# audibleCore.net
KiCad netlist of a schematic drawn in EAGLE
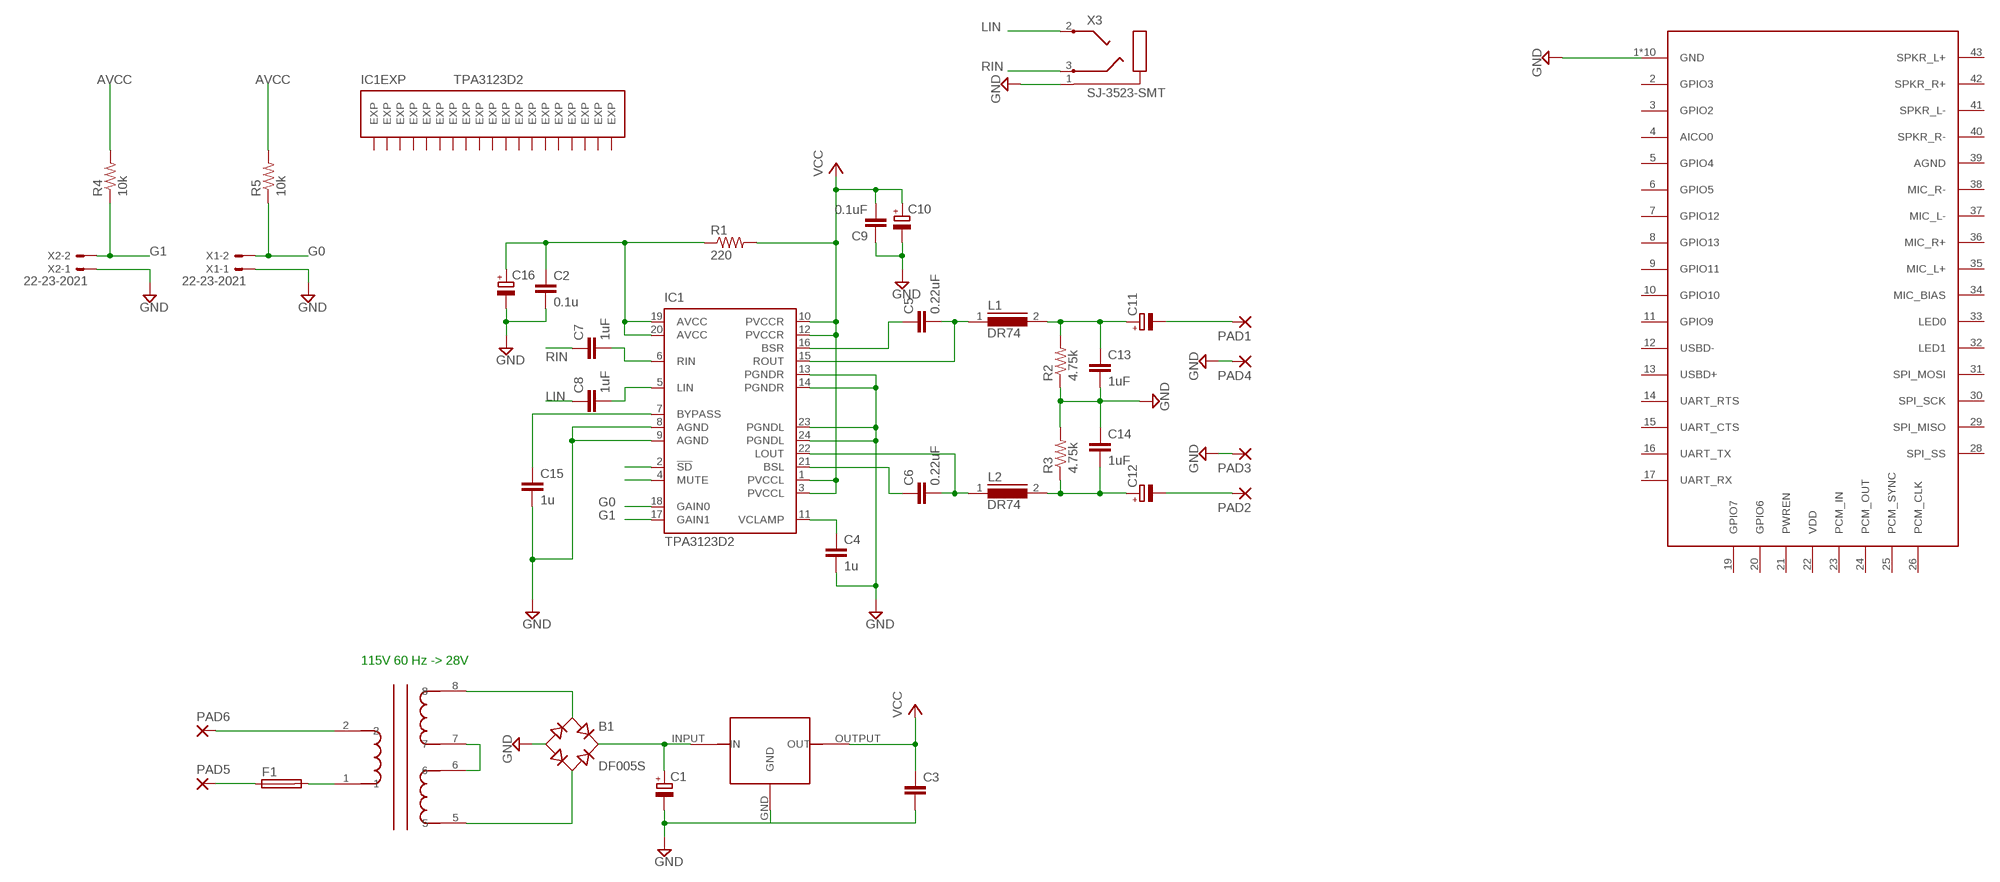
[diagram p0: schematic, sheet 1]

(export (version "E")
  (design (tool "Eeschema 10.0.6"))
  (components
    (comp (ref "B1")
      (value "DF005S")
      (footprint "eagle-import:DFS")
      (libsource (lib "eagle-import") (part "DFS005"))
    )
    (comp (ref "C1")
      (value "CPOL-EUG")
      (footprint "eagle-import:PANASONIC_G")
      (libsource (lib "eagle-import") (part "CPOL-EUG"))
    )
    (comp (ref "C2")
      (value "0.1u")
      (footprint "eagle-import:C1206")
      (libsource (lib "eagle-import") (part "C-EUC1206"))
    )
    (comp (ref "C3")
      (value "C-EUC1206")
      (footprint "eagle-import:C1206")
      (libsource (lib "eagle-import") (part "C-EUC1206"))
    )
    (comp (ref "C4")
      (value "1u")
      (footprint "eagle-import:C1206")
      (libsource (lib "eagle-import") (part "C-EUC1206"))
    )
    (comp (ref "C5")
      (value "0.22uF")
      (footprint "eagle-import:C1206")
      (libsource (lib "eagle-import") (part "C-EUC1206"))
    )
    (comp (ref "C6")
      (value "0.22uF")
      (footprint "eagle-import:C1206")
      (libsource (lib "eagle-import") (part "C-EUC1206"))
    )
    (comp (ref "C7")
      (value "1uF")
      (footprint "eagle-import:C1206")
      (libsource (lib "eagle-import") (part "C-EUC1206"))
    )
    (comp (ref "C8")
      (value "1uF")
      (footprint "eagle-import:C1206")
      (libsource (lib "eagle-import") (part "C-EUC1206"))
    )
    (comp (ref "C9")
      (value "0.1uF")
      (footprint "eagle-import:C1206")
      (libsource (lib "eagle-import") (part "C-EUC1206"))
    )
    (comp (ref "C10")
      (value "CPOL-EUG")
      (footprint "eagle-import:PANASONIC_G")
      (libsource (lib "eagle-import") (part "CPOL-EUG"))
    )
    (comp (ref "C11")
      (value "CPOL-EUG")
      (footprint "eagle-import:PANASONIC_G")
      (libsource (lib "eagle-import") (part "CPOL-EUG"))
    )
    (comp (ref "C12")
      (value "CPOL-EUG")
      (footprint "eagle-import:PANASONIC_G")
      (libsource (lib "eagle-import") (part "CPOL-EUG"))
    )
    (comp (ref "C13")
      (value "1uF")
      (footprint "eagle-import:C1206")
      (libsource (lib "eagle-import") (part "C-EUC1206"))
    )
    (comp (ref "C14")
      (value "1uF")
      (footprint "eagle-import:C1206")
      (libsource (lib "eagle-import") (part "C-EUC1206"))
    )
    (comp (ref "C15")
      (value "1u")
      (footprint "eagle-import:C1206")
      (libsource (lib "eagle-import") (part "C-EUC1206"))
    )
    (comp (ref "C16")
      (value "CPOL-EUG")
      (footprint "eagle-import:PANASONIC_G")
      (libsource (lib "eagle-import") (part "CPOL-EUG"))
    )
    (comp (ref "F1")
      (value "GSH15")
      (footprint "eagle-import:GSH15")
      (fields (field (name "MPN") "64900001039"))
      (libsource (lib "eagle-import") (part "GSH15"))
    )
    (comp (ref "IC1")
      (value "TPA3123D2")
      (footprint "eagle-import:PWP-TSSOP24")
      (fields (field (name "MPN") "TPA3123D2PWP"))
      (libsource (lib "eagle-import") (part "TPA3123D2"))
    )
    (comp (ref "L1")
      (value "DR74")
      (footprint "eagle-import:DR74")
      (libsource (lib "eagle-import") (part "DR74"))
    )
    (comp (ref "L2")
      (value "DR74")
      (footprint "eagle-import:DR74")
      (libsource (lib "eagle-import") (part "DR74"))
    )
    (comp (ref "PAD1")
      (value "SMD5")
      (footprint "eagle-import:SMD2,54-5,08")
      (libsource (lib "eagle-import") (part "SMD5"))
    )
    (comp (ref "PAD2")
      (value "SMD5")
      (footprint "eagle-import:SMD2,54-5,08")
      (libsource (lib "eagle-import") (part "SMD5"))
    )
    (comp (ref "PAD3")
      (value "SMD5")
      (footprint "eagle-import:SMD2,54-5,08")
      (libsource (lib "eagle-import") (part "SMD5"))
    )
    (comp (ref "PAD4")
      (value "SMD5")
      (footprint "eagle-import:SMD2,54-5,08")
      (libsource (lib "eagle-import") (part "SMD5"))
    )
    (comp (ref "PAD5")
      (value "SMD5")
      (footprint "eagle-import:SMD2,54-5,08")
      (libsource (lib "eagle-import") (part "SMD5"))
    )
    (comp (ref "PAD6")
      (value "SMD5")
      (footprint "eagle-import:SMD2,54-5,08")
      (libsource (lib "eagle-import") (part "SMD5"))
    )
    (comp (ref "R1")
      (value "220")
      (footprint "eagle-import:R1206")
      (libsource (lib "eagle-import") (part "R-US_R1206"))
    )
    (comp (ref "R2")
      (value "4.75k")
      (footprint "eagle-import:R1206")
      (libsource (lib "eagle-import") (part "R-US_R1206"))
    )
    (comp (ref "R3")
      (value "4.75k")
      (footprint "eagle-import:R1206")
      (libsource (lib "eagle-import") (part "R-US_R1206"))
    )
    (comp (ref "R4")
      (value "10k")
      (footprint "eagle-import:R1206")
      (libsource (lib "eagle-import") (part "R-US_R1206"))
    )
    (comp (ref "R5")
      (value "10k")
      (footprint "eagle-import:R1206")
      (libsource (lib "eagle-import") (part "R-US_R1206"))
    )
    (comp (ref "U$1")
      (value "ST-7-24")
      (footprint "eagle-import:ST-7")
      (libsource (lib "eagle-import") (part "ST-7-24"))
    )
    (comp (ref "U$2")
      (value "L78XX")
      (footprint "eagle-import:D2PAK")
      (libsource (lib "eagle-import") (part "L78XX"))
    )
    (comp (ref "U$3")
      (value "RN-52")
      (footprint "eagle-import:RN-52")
      (libsource (lib "eagle-import") (part "RN-52"))
    )
    (comp (ref "X1")
      (value "22-23-2021")
      (footprint "eagle-import:22-23-2021")
      (fields (field (name "MF") "MOLEX"))
      (libsource (lib "eagle-import") (part "22-23-2021"))
    )
    (comp (ref "X2")
      (value "22-23-2021")
      (footprint "eagle-import:22-23-2021")
      (fields (field (name "MF") "MOLEX"))
      (libsource (lib "eagle-import") (part "22-23-2021"))
    )
    (comp (ref "X3")
      (value "SJ-3523-SMT")
      (footprint "eagle-import:SJ-3523-SMT")
      (libsource (lib "eagle-import") (part "SJ-3523-SMT"))
    )
  )
  (nets
    (net (code "1") (name "/AVCC") (class "Default")
      (node (ref "C16") (pin "+") (pinfunction "+_+") (pintype "passive"))
      (node (ref "C2") (pin "1") (pinfunction "1_1") (pintype "passive"))
      (node (ref "IC1") (pin "19") (pinfunction "AVCC_19") (pintype "input"))
      (node (ref "IC1") (pin "20") (pinfunction "AVCC_20") (pintype "input"))
      (node (ref "R1") (pin "1") (pinfunction "1_1") (pintype "passive"))
      (node (ref "R4") (pin "2") (pinfunction "2_2") (pintype "passive"))
      (node (ref "R5") (pin "2") (pinfunction "2_2") (pintype "passive"))
    )
    (net (code "2") (name "/G0") (class "Default")
      (node (ref "IC1") (pin "18") (pinfunction "GAIN0_18") (pintype "input"))
      (node (ref "R5") (pin "1") (pinfunction "1_1") (pintype "passive"))
      (node (ref "X1") (pin "2") (pinfunction "S_2") (pintype "passive"))
    )
    (net (code "3") (name "/G1") (class "Default")
      (node (ref "IC1") (pin "17") (pinfunction "GAIN1_17") (pintype "input"))
      (node (ref "R4") (pin "1") (pinfunction "1_1") (pintype "passive"))
      (node (ref "X2") (pin "2") (pinfunction "S_2") (pintype "passive"))
    )
    (net (code "4") (name "/LIN") (class "Default")
      (node (ref "C8") (pin "1") (pinfunction "1_1") (pintype "passive"))
      (node (ref "X3") (pin "2") (pinfunction "TIP_2") (pintype "passive"))
    )
    (net (code "5") (name "/RIN") (class "Default")
      (node (ref "C7") (pin "1") (pinfunction "1_1") (pintype "passive"))
      (node (ref "X3") (pin "3") (pinfunction "RING_3") (pintype "passive"))
    )
    (net (code "6") (name "GND") (class "Default")
      (node (ref "B1") (pin "-") (pinfunction "-_-") (pintype "passive"))
      (node (ref "C1") (pin "-") (pinfunction "-_-") (pintype "passive"))
      (node (ref "C10") (pin "-") (pinfunction "-_-") (pintype "passive"))
      (node (ref "C13") (pin "2") (pinfunction "2_2") (pintype "passive"))
      (node (ref "C14") (pin "1") (pinfunction "1_1") (pintype "passive"))
      (node (ref "C15") (pin "2") (pinfunction "2_2") (pintype "passive"))
      (node (ref "C16") (pin "-") (pinfunction "-_-") (pintype "passive"))
      (node (ref "C2") (pin "2") (pinfunction "2_2") (pintype "passive"))
      (node (ref "C3") (pin "2") (pinfunction "2_2") (pintype "passive"))
      (node (ref "C4") (pin "2") (pinfunction "2_2") (pintype "passive"))
      (node (ref "C9") (pin "1") (pinfunction "1_1") (pintype "passive"))
      (node (ref "IC1") (pin "13") (pinfunction "PGNDR_13") (pintype "input"))
      (node (ref "IC1") (pin "14") (pinfunction "PGNDR_14") (pintype "input"))
      (node (ref "IC1") (pin "23") (pinfunction "PGNDL_23") (pintype "input"))
      (node (ref "IC1") (pin "24") (pinfunction "PGNDL_24") (pintype "input"))
      (node (ref "IC1") (pin "8") (pinfunction "AGND_8") (pintype "input"))
      (node (ref "IC1") (pin "9") (pinfunction "AGND_9") (pintype "input"))
      (node (ref "PAD3") (pin "1") (pinfunction "P_1") (pintype "passive"))
      (node (ref "PAD4") (pin "1") (pinfunction "P_1") (pintype "passive"))
      (node (ref "R2") (pin "1") (pinfunction "1_1") (pintype "passive"))
      (node (ref "R3") (pin "2") (pinfunction "2_2") (pintype "passive"))
      (node (ref "U$2") (pin "GND") (pinfunction "GND_GND") (pintype "bidirectional"))
      (node (ref "U$3") (pin "1") (pinfunction "GND_1") (pintype "bidirectional"))
      (node (ref "U$3") (pin "18") (pinfunction "GND_18") (pintype "bidirectional"))
      (node (ref "U$3") (pin "27") (pinfunction "GND_27") (pintype "bidirectional"))
      (node (ref "U$3") (pin "44") (pinfunction "GND_44") (pintype "bidirectional"))
      (node (ref "U$3") (pin "45") (pinfunction "GND_45") (pintype "bidirectional"))
      (node (ref "U$3") (pin "46") (pinfunction "GND_46") (pintype "bidirectional"))
      (node (ref "U$3") (pin "47") (pinfunction "GND_47") (pintype "bidirectional"))
      (node (ref "U$3") (pin "48") (pinfunction "GND_48") (pintype "bidirectional"))
      (node (ref "U$3") (pin "49") (pinfunction "GND_49") (pintype "bidirectional"))
      (node (ref "U$3") (pin "50") (pinfunction "GND_50") (pintype "bidirectional"))
      (node (ref "X1") (pin "1") (pinfunction "S_1") (pintype "passive"))
      (node (ref "X2") (pin "1") (pinfunction "S_1") (pintype "passive"))
      (node (ref "X3") (pin "1") (pinfunction "EARTH_1") (pintype "passive"))
    )
    (net (code "7") (name "Net-(B1-PadAC1)") (class "Default")
      (node (ref "B1") (pin "AC1") (pinfunction "AC1_AC1") (pintype "passive"))
      (node (ref "U$1") (pin "8") (pinfunction "8_8") (pintype "bidirectional"))
    )
    (net (code "8") (name "Net-(B1-PadAC2)") (class "Default")
      (node (ref "B1") (pin "AC2") (pinfunction "AC2_AC2") (pintype "passive"))
      (node (ref "U$1") (pin "5") (pinfunction "5_5") (pintype "bidirectional"))
    )
    (net (code "9") (name "Net-(C11-Pad+)") (class "Default")
      (node (ref "C11") (pin "+") (pinfunction "+_+") (pintype "passive"))
      (node (ref "C13") (pin "1") (pinfunction "1_1") (pintype "passive"))
      (node (ref "L1") (pin "2") (pinfunction "2_2") (pintype "passive"))
      (node (ref "R2") (pin "2") (pinfunction "2_2") (pintype "passive"))
    )
    (net (code "10") (name "Net-(C12-Pad+)") (class "Default")
      (node (ref "C12") (pin "+") (pinfunction "+_+") (pintype "passive"))
      (node (ref "C14") (pin "2") (pinfunction "2_2") (pintype "passive"))
      (node (ref "L2") (pin "2") (pinfunction "2_2") (pintype "passive"))
      (node (ref "R3") (pin "1") (pinfunction "1_1") (pintype "passive"))
    )
    (net (code "11") (name "Net-(F1-Pad2)") (class "Default")
      (node (ref "F1") (pin "2") (pinfunction "2_2") (pintype "passive"))
      (node (ref "U$1") (pin "1") (pinfunction "1_1") (pintype "bidirectional"))
    )
    (net (code "12") (name "Net-(IC1B-BSL)") (class "Default")
      (node (ref "C6") (pin "1") (pinfunction "1_1") (pintype "passive"))
      (node (ref "IC1") (pin "21") (pinfunction "BSL_21") (pintype "passive"))
    )
    (net (code "13") (name "Net-(IC1B-BSR)") (class "Default")
      (node (ref "C5") (pin "1") (pinfunction "1_1") (pintype "passive"))
      (node (ref "IC1") (pin "16") (pinfunction "BSR_16") (pintype "passive"))
    )
    (net (code "14") (name "Net-(IC1B-BYPASS)") (class "Default")
      (node (ref "C15") (pin "1") (pinfunction "1_1") (pintype "passive"))
      (node (ref "IC1") (pin "7") (pinfunction "BYPASS_7") (pintype "input"))
    )
    (net (code "15") (name "Net-(IC1B-LIN)") (class "Default")
      (node (ref "C8") (pin "2") (pinfunction "2_2") (pintype "passive"))
      (node (ref "IC1") (pin "5") (pinfunction "LIN_5") (pintype "input"))
    )
    (net (code "16") (name "Net-(IC1B-LOUT)") (class "Default")
      (node (ref "C6") (pin "2") (pinfunction "2_2") (pintype "passive"))
      (node (ref "IC1") (pin "22") (pinfunction "LOUT_22") (pintype "output"))
      (node (ref "L2") (pin "1") (pinfunction "1_1") (pintype "passive"))
    )
    (net (code "17") (name "Net-(IC1B-RIN)") (class "Default")
      (node (ref "C7") (pin "2") (pinfunction "2_2") (pintype "passive"))
      (node (ref "IC1") (pin "6") (pinfunction "RIN_6") (pintype "input"))
    )
    (net (code "18") (name "Net-(IC1B-ROUT)") (class "Default")
      (node (ref "C5") (pin "2") (pinfunction "2_2") (pintype "passive"))
      (node (ref "IC1") (pin "15") (pinfunction "ROUT_15") (pintype "output"))
      (node (ref "L1") (pin "1") (pinfunction "1_1") (pintype "passive"))
    )
    (net (code "19") (name "Net-(IC1B-VCLAMP)") (class "Default")
      (node (ref "C4") (pin "1") (pinfunction "1_1") (pintype "passive"))
      (node (ref "IC1") (pin "11") (pinfunction "VCLAMP_11") (pintype "input"))
    )
    (net (code "20") (name "Net-(PAD1-P)") (class "Default")
      (node (ref "C11") (pin "-") (pinfunction "-_-") (pintype "passive"))
      (node (ref "PAD1") (pin "1") (pinfunction "P_1") (pintype "passive"))
    )
    (net (code "21") (name "Net-(PAD2-P)") (class "Default")
      (node (ref "C12") (pin "-") (pinfunction "-_-") (pintype "passive"))
      (node (ref "PAD2") (pin "1") (pinfunction "P_1") (pintype "passive"))
    )
    (net (code "22") (name "Net-(PAD5-P)") (class "Default")
      (node (ref "F1") (pin "1") (pinfunction "1_1") (pintype "passive"))
      (node (ref "PAD5") (pin "1") (pinfunction "P_1") (pintype "passive"))
    )
    (net (code "23") (name "Net-(PAD6-P)") (class "Default")
      (node (ref "PAD6") (pin "1") (pinfunction "P_1") (pintype "passive"))
      (node (ref "U$1") (pin "2") (pinfunction "2_2") (pintype "bidirectional"))
    )
    (net (code "24") (name "Net-(U$1-Pad6)") (class "Default")
      (node (ref "U$1") (pin "6") (pinfunction "6_6") (pintype "bidirectional"))
      (node (ref "U$1") (pin "7") (pinfunction "7_7") (pintype "bidirectional"))
    )
    (net (code "25") (name "Net-(U$2-IN)") (class "Default")
      (node (ref "B1") (pin "+") (pinfunction "+_+") (pintype "passive"))
      (node (ref "C1") (pin "+") (pinfunction "+_+") (pintype "passive"))
      (node (ref "U$2") (pin "INPUT") (pinfunction "IN_INPUT") (pintype "bidirectional"))
    )
    (net (code "26") (name "VCC") (class "Default")
      (node (ref "C10") (pin "+") (pinfunction "+_+") (pintype "passive"))
      (node (ref "C3") (pin "1") (pinfunction "1_1") (pintype "passive"))
      (node (ref "C9") (pin "2") (pinfunction "2_2") (pintype "passive"))
      (node (ref "IC1") (pin "1") (pinfunction "PVCCL_1") (pintype "input"))
      (node (ref "IC1") (pin "10") (pinfunction "PVCCR_10") (pintype "input"))
      (node (ref "IC1") (pin "12") (pinfunction "PVCCR_12") (pintype "input"))
      (node (ref "IC1") (pin "3") (pinfunction "PVCCL_3") (pintype "input"))
      (node (ref "R1") (pin "2") (pinfunction "2_2") (pintype "passive"))
      (node (ref "U$2") (pin "OUTPUT") (pinfunction "OUT_OUTPUT") (pintype "bidirectional"))
    )
    (net (code "27") (name "unconnected-(IC1-PadEXP)") (class "Default")
      (node (ref "IC1") (pin "EXP") (pinfunction "EXP_EXP") (pintype "passive"))
    )
    (net (code "28") (name "unconnected-(IC1A-EXP-PadEXP@1)") (class "Default")
      (node (ref "IC1") (pin "EXP@1") (pinfunction "EXP_EXP@1") (pintype "passive"))
    )
    (net (code "29") (name "unconnected-(IC1A-EXP-PadEXP@2)") (class "Default")
      (node (ref "IC1") (pin "EXP@2") (pinfunction "EXP_EXP@2") (pintype "passive"))
    )
    (net (code "30") (name "unconnected-(IC1A-EXP-PadEXP@3)") (class "Default")
      (node (ref "IC1") (pin "EXP@3") (pinfunction "EXP_EXP@3") (pintype "passive"))
    )
    (net (code "31") (name "unconnected-(IC1A-EXP-PadEXP@4)") (class "Default")
      (node (ref "IC1") (pin "EXP@4") (pinfunction "EXP_EXP@4") (pintype "passive"))
    )
    (net (code "32") (name "unconnected-(IC1A-EXP-PadEXP@5)") (class "Default")
      (node (ref "IC1") (pin "EXP@5") (pinfunction "EXP_EXP@5") (pintype "passive"))
    )
    (net (code "33") (name "unconnected-(IC1A-EXP-PadEXP@6)") (class "Default")
      (node (ref "IC1") (pin "EXP@6") (pinfunction "EXP_EXP@6") (pintype "passive"))
    )
    (net (code "34") (name "unconnected-(IC1A-EXP-PadEXP@7)") (class "Default")
      (node (ref "IC1") (pin "EXP@7") (pinfunction "EXP_EXP@7") (pintype "passive"))
    )
    (net (code "35") (name "unconnected-(IC1A-EXP-PadEXP@8)") (class "Default")
      (node (ref "IC1") (pin "EXP@8") (pinfunction "EXP_EXP@8") (pintype "passive"))
    )
    (net (code "36") (name "unconnected-(IC1A-EXP-PadEXP@9)") (class "Default")
      (node (ref "IC1") (pin "EXP@9") (pinfunction "EXP_EXP@9") (pintype "passive"))
    )
    (net (code "37") (name "unconnected-(IC1A-EXP-PadEXP@10)") (class "Default")
      (node (ref "IC1") (pin "EXP@10") (pinfunction "EXP_EXP@10") (pintype "passive"))
    )
    (net (code "38") (name "unconnected-(IC1A-EXP-PadEXP@11)") (class "Default")
      (node (ref "IC1") (pin "EXP@11") (pinfunction "EXP_EXP@11") (pintype "passive"))
    )
    (net (code "39") (name "unconnected-(IC1A-EXP-PadEXP@12)") (class "Default")
      (node (ref "IC1") (pin "EXP@12") (pinfunction "EXP_EXP@12") (pintype "passive"))
    )
    (net (code "40") (name "unconnected-(IC1A-EXP-PadEXP@13)") (class "Default")
      (node (ref "IC1") (pin "EXP@13") (pinfunction "EXP_EXP@13") (pintype "passive"))
    )
    (net (code "41") (name "unconnected-(IC1A-EXP-PadEXP@14)") (class "Default")
      (node (ref "IC1") (pin "EXP@14") (pinfunction "EXP_EXP@14") (pintype "passive"))
    )
    (net (code "42") (name "unconnected-(IC1A-EXP-PadEXP@15)") (class "Default")
      (node (ref "IC1") (pin "EXP@15") (pinfunction "EXP_EXP@15") (pintype "passive"))
    )
    (net (code "43") (name "unconnected-(IC1A-EXP-PadEXP@16)") (class "Default")
      (node (ref "IC1") (pin "EXP@16") (pinfunction "EXP_EXP@16") (pintype "passive"))
    )
    (net (code "44") (name "unconnected-(IC1A-EXP-PadEXP@17)") (class "Default")
      (node (ref "IC1") (pin "EXP@17") (pinfunction "EXP_EXP@17") (pintype "passive"))
    )
    (net (code "45") (name "unconnected-(IC1A-EXP-PadEXP@18)") (class "Default")
      (node (ref "IC1") (pin "EXP@18") (pinfunction "EXP_EXP@18") (pintype "passive"))
    )
    (net (code "46") (name "unconnected-(IC1B-MUTE-Pad4)") (class "Default")
      (node (ref "IC1") (pin "4") (pinfunction "MUTE_4") (pintype "input"))
    )
    (net (code "47") (name "unconnected-(IC1B-~{SD}-Pad2)") (class "Default")
      (node (ref "IC1") (pin "2") (pinfunction "~{SD}_2") (pintype "input"))
    )
    (net (code "48") (name "unconnected-(U$3-AGND-Pad39)") (class "Default")
      (node (ref "U$3") (pin "39") (pinfunction "AGND_39") (pintype "bidirectional"))
    )
    (net (code "49") (name "unconnected-(U$3-AICO0-Pad4)") (class "Default")
      (node (ref "U$3") (pin "4") (pinfunction "AICO0_4") (pintype "bidirectional"))
    )
    (net (code "50") (name "unconnected-(U$3-GPIO2-Pad3)") (class "Default")
      (node (ref "U$3") (pin "3") (pinfunction "GPIO2_3") (pintype "bidirectional"))
    )
    (net (code "51") (name "unconnected-(U$3-GPIO3-Pad2)") (class "Default")
      (node (ref "U$3") (pin "2") (pinfunction "GPIO3_2") (pintype "bidirectional"))
    )
    (net (code "52") (name "unconnected-(U$3-GPIO4-Pad5)") (class "Default")
      (node (ref "U$3") (pin "5") (pinfunction "GPIO4_5") (pintype "bidirectional"))
    )
    (net (code "53") (name "unconnected-(U$3-GPIO5-Pad6)") (class "Default")
      (node (ref "U$3") (pin "6") (pinfunction "GPIO5_6") (pintype "bidirectional"))
    )
    (net (code "54") (name "unconnected-(U$3-GPIO6-Pad20)") (class "Default")
      (node (ref "U$3") (pin "20") (pinfunction "GPIO6_20") (pintype "bidirectional"))
    )
    (net (code "55") (name "unconnected-(U$3-GPIO7-Pad19)") (class "Default")
      (node (ref "U$3") (pin "19") (pinfunction "GPIO7_19") (pintype "bidirectional"))
    )
    (net (code "56") (name "unconnected-(U$3-GPIO9-Pad11)") (class "Default")
      (node (ref "U$3") (pin "11") (pinfunction "GPIO9_11") (pintype "bidirectional"))
    )
    (net (code "57") (name "unconnected-(U$3-GPIO10-Pad10)") (class "Default")
      (node (ref "U$3") (pin "10") (pinfunction "GPIO10_10") (pintype "bidirectional"))
    )
    (net (code "58") (name "unconnected-(U$3-GPIO11-Pad9)") (class "Default")
      (node (ref "U$3") (pin "9") (pinfunction "GPIO11_9") (pintype "bidirectional"))
    )
    (net (code "59") (name "unconnected-(U$3-GPIO12-Pad7)") (class "Default")
      (node (ref "U$3") (pin "7") (pinfunction "GPIO12_7") (pintype "bidirectional"))
    )
    (net (code "60") (name "unconnected-(U$3-GPIO13-Pad8)") (class "Default")
      (node (ref "U$3") (pin "8") (pinfunction "GPIO13_8") (pintype "bidirectional"))
    )
    (net (code "61") (name "unconnected-(U$3-LED0-Pad33)") (class "Default")
      (node (ref "U$3") (pin "33") (pinfunction "LED0_33") (pintype "bidirectional"))
    )
    (net (code "62") (name "unconnected-(U$3-LED1-Pad32)") (class "Default")
      (node (ref "U$3") (pin "32") (pinfunction "LED1_32") (pintype "bidirectional"))
    )
    (net (code "63") (name "unconnected-(U$3-MIC_BIAS-Pad34)") (class "Default")
      (node (ref "U$3") (pin "34") (pinfunction "MIC_BIAS_34") (pintype "bidirectional"))
    )
    (net (code "64") (name "unconnected-(U$3-MIC_L+-Pad35)") (class "Default")
      (node (ref "U$3") (pin "35") (pinfunction "MIC_L+_35") (pintype "bidirectional"))
    )
    (net (code "65") (name "unconnected-(U$3-MIC_L--Pad37)") (class "Default")
      (node (ref "U$3") (pin "37") (pinfunction "MIC_L-_37") (pintype "bidirectional"))
    )
    (net (code "66") (name "unconnected-(U$3-MIC_R+-Pad36)") (class "Default")
      (node (ref "U$3") (pin "36") (pinfunction "MIC_R+_36") (pintype "bidirectional"))
    )
    (net (code "67") (name "unconnected-(U$3-MIC_R--Pad38)") (class "Default")
      (node (ref "U$3") (pin "38") (pinfunction "MIC_R-_38") (pintype "bidirectional"))
    )
    (net (code "68") (name "unconnected-(U$3-PCM_CLK-Pad26)") (class "Default")
      (node (ref "U$3") (pin "26") (pinfunction "PCM_CLK_26") (pintype "bidirectional"))
    )
    (net (code "69") (name "unconnected-(U$3-PCM_IN-Pad23)") (class "Default")
      (node (ref "U$3") (pin "23") (pinfunction "PCM_IN_23") (pintype "bidirectional"))
    )
    (net (code "70") (name "unconnected-(U$3-PCM_OUT-Pad24)") (class "Default")
      (node (ref "U$3") (pin "24") (pinfunction "PCM_OUT_24") (pintype "bidirectional"))
    )
    (net (code "71") (name "unconnected-(U$3-PCM_SYNC-Pad25)") (class "Default")
      (node (ref "U$3") (pin "25") (pinfunction "PCM_SYNC_25") (pintype "bidirectional"))
    )
    (net (code "72") (name "unconnected-(U$3-PWREN-Pad21)") (class "Default")
      (node (ref "U$3") (pin "21") (pinfunction "PWREN_21") (pintype "bidirectional"))
    )
    (net (code "73") (name "unconnected-(U$3-SPI_MISO-Pad29)") (class "Default")
      (node (ref "U$3") (pin "29") (pinfunction "SPI_MISO_29") (pintype "bidirectional"))
    )
    (net (code "74") (name "unconnected-(U$3-SPI_MOSI-Pad31)") (class "Default")
      (node (ref "U$3") (pin "31") (pinfunction "SPI_MOSI_31") (pintype "bidirectional"))
    )
    (net (code "75") (name "unconnected-(U$3-SPI_SCK-Pad30)") (class "Default")
      (node (ref "U$3") (pin "30") (pinfunction "SPI_SCK_30") (pintype "bidirectional"))
    )
    (net (code "76") (name "unconnected-(U$3-SPI_SS-Pad28)") (class "Default")
      (node (ref "U$3") (pin "28") (pinfunction "SPI_SS_28") (pintype "bidirectional"))
    )
    (net (code "77") (name "unconnected-(U$3-SPKR_L+-Pad43)") (class "Default")
      (node (ref "U$3") (pin "43") (pinfunction "SPKR_L+_43") (pintype "bidirectional"))
    )
    (net (code "78") (name "unconnected-(U$3-SPKR_L--Pad41)") (class "Default")
      (node (ref "U$3") (pin "41") (pinfunction "SPKR_L-_41") (pintype "bidirectional"))
    )
    (net (code "79") (name "unconnected-(U$3-SPKR_R+-Pad42)") (class "Default")
      (node (ref "U$3") (pin "42") (pinfunction "SPKR_R+_42") (pintype "bidirectional"))
    )
    (net (code "80") (name "unconnected-(U$3-SPKR_R--Pad40)") (class "Default")
      (node (ref "U$3") (pin "40") (pinfunction "SPKR_R-_40") (pintype "bidirectional"))
    )
    (net (code "81") (name "unconnected-(U$3-UART_CTS-Pad15)") (class "Default")
      (node (ref "U$3") (pin "15") (pinfunction "UART_CTS_15") (pintype "bidirectional"))
    )
    (net (code "82") (name "unconnected-(U$3-UART_RTS-Pad14)") (class "Default")
      (node (ref "U$3") (pin "14") (pinfunction "UART_RTS_14") (pintype "bidirectional"))
    )
    (net (code "83") (name "unconnected-(U$3-UART_RX-Pad17)") (class "Default")
      (node (ref "U$3") (pin "17") (pinfunction "UART_RX_17") (pintype "bidirectional"))
    )
    (net (code "84") (name "unconnected-(U$3-UART_TX-Pad16)") (class "Default")
      (node (ref "U$3") (pin "16") (pinfunction "UART_TX_16") (pintype "bidirectional"))
    )
    (net (code "85") (name "unconnected-(U$3-USBD+-Pad13)") (class "Default")
      (node (ref "U$3") (pin "13") (pinfunction "USBD+_13") (pintype "bidirectional"))
    )
    (net (code "86") (name "unconnected-(U$3-USBD--Pad12)") (class "Default")
      (node (ref "U$3") (pin "12") (pinfunction "USBD-_12") (pintype "bidirectional"))
    )
    (net (code "87") (name "unconnected-(U$3-VDD-Pad22)") (class "Default")
      (node (ref "U$3") (pin "22") (pinfunction "VDD_22") (pintype "bidirectional"))
    )
  )
)
